# Zoetrope.net
KiCad netlist of a schematic drawn in EAGLE
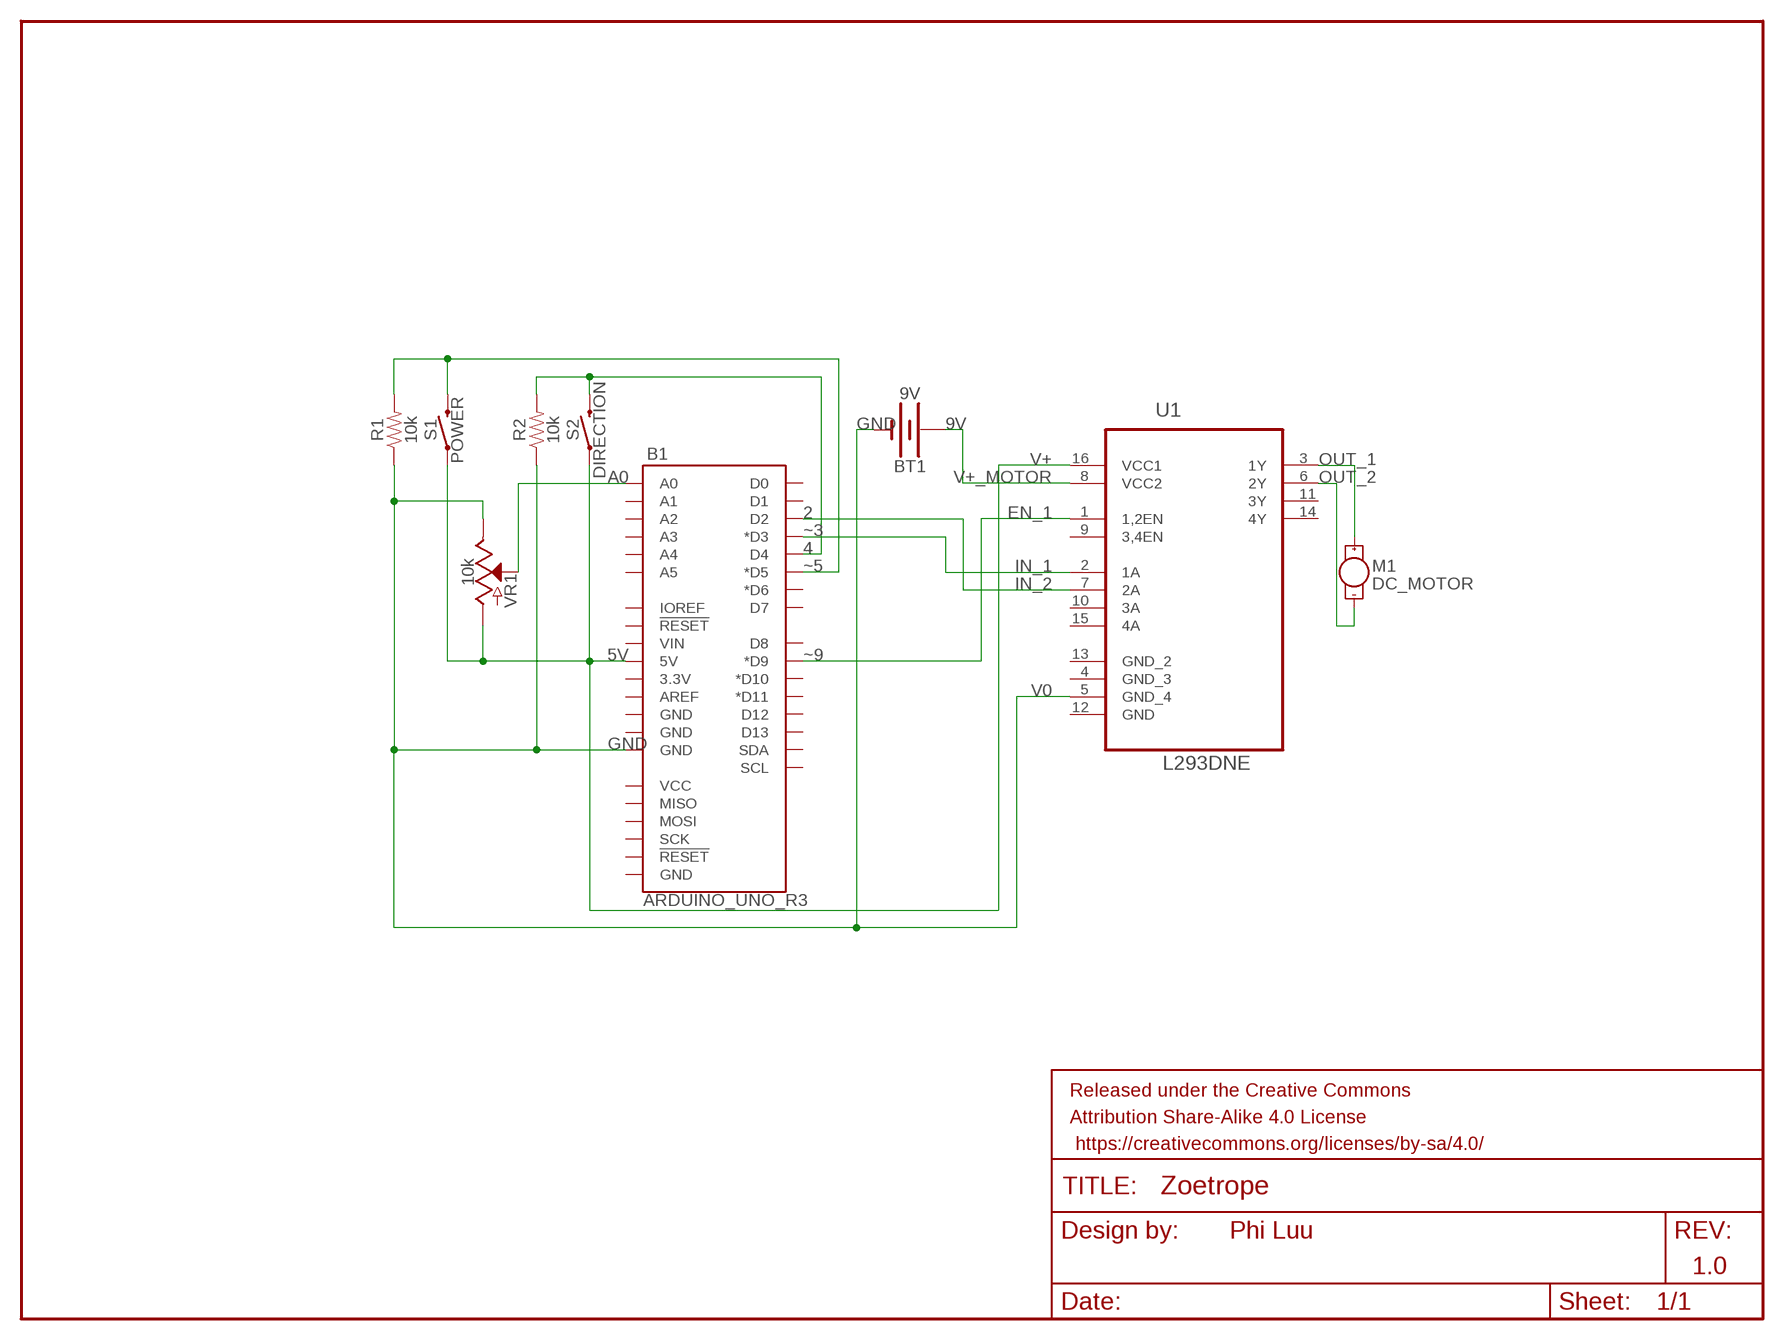
[diagram p0: schematic, sheet 1]

(export (version "E")
  (design (tool "Eeschema 10.0.6"))
  (components
    (comp (ref "B1")
      (value "ARDUINO_UNO_R3")
      (footprint "eagle-import:ARDUINO_R3")
      (libsource (lib "eagle-import") (part "ARDUINO_UNO_R3"))
    )
    (comp (ref "BT1")
      (value "9V")
      (footprint "eagle-import:BATTCON_9V")
      (libsource (lib "eagle-import") (part "BATTERY-9V"))
    )
    (comp (ref "FRAME1")
      (value "FRAME-LETTER")
      (footprint "eagle-import:CREATIVE_COMMONS")
      (libsource (lib "eagle-import") (part "FRAME-LETTER"))
    )
    (comp (ref "M1")
      (value "DC_MOTOR")
      (footprint "eagle-import:VIBE-MOTOR-10MM")
      (libsource (lib "eagle-import") (part "MOTOR10MM"))
    )
    (comp (ref "R1")
      (value "10k")
      (footprint "eagle-import:AXIAL-0.3")
      (libsource (lib "eagle-import") (part "10KOHM-HORIZ-1/4W-5%"))
    )
    (comp (ref "R2")
      (value "10k")
      (footprint "eagle-import:AXIAL-0.3")
      (libsource (lib "eagle-import") (part "10KOHM-HORIZ-1/4W-5%"))
    )
    (comp (ref "S1")
      (value "POWER")
      (footprint "eagle-import:TACTILE_SWITCH_PTH_6.0MM")
      (libsource (lib "eagle-import") (part "MOMENTARY-SWITCH-SPST-PTH-6.0MM"))
    )
    (comp (ref "S2")
      (value "DIRECTION")
      (footprint "eagle-import:TACTILE_SWITCH_PTH_6.0MM")
      (libsource (lib "eagle-import") (part "MOMENTARY-SWITCH-SPST-PTH-6.0MM"))
    )
    (comp (ref "U1")
      (value "L293DNE")
      (footprint "eagle-import:DIP254P762X508-16")
      (libsource (lib "eagle-import") (part "L293DNE"))
    )
    (comp (ref "VR1")
      (value "10k")
      (footprint "eagle-import:POT-PTH-ALPS")
      (libsource (lib "eagle-import") (part "POTENTIOMETER-PTH-9MM-1/20W-20%"))
    )
  )
  (nets
    (net (code "1") (name "/2") (class "Default")
      (node (ref "B1") (pin "D2") (pinfunction "D2_D2") (pintype "bidirectional"))
      (node (ref "U1") (pin "7") (pinfunction "2A_7") (pintype "input"))
    )
    (net (code "2") (name "/4") (class "Default")
      (node (ref "B1") (pin "D4") (pinfunction "D4_D4") (pintype "bidirectional"))
      (node (ref "R2") (pin "P$2") (pinfunction "2_P$2") (pintype "passive"))
      (node (ref "S2") (pin "3") (pinfunction "2_3") (pintype "passive"))
    )
    (net (code "3") (name "/5V") (class "Default")
      (node (ref "B1") (pin "5V") (pinfunction "5V_5V") (pintype "bidirectional"))
      (node (ref "S1") (pin "1") (pinfunction "1_1") (pintype "passive"))
      (node (ref "S2") (pin "1") (pinfunction "1_1") (pintype "passive"))
      (node (ref "U1") (pin "16") (pinfunction "VCC1_16") (pintype "power_in"))
      (node (ref "VR1") (pin "P$3") (pinfunction "A_P$3") (pintype "passive"))
    )
    (net (code "4") (name "/9V") (class "Default")
      (node (ref "BT1") (pin "+") (pinfunction "+_+") (pintype "power_in"))
      (node (ref "U1") (pin "8") (pinfunction "VCC2_8") (pintype "power_in"))
    )
    (net (code "5") (name "/A0") (class "Default")
      (node (ref "B1") (pin "A0") (pinfunction "A0_A0") (pintype "bidirectional"))
      (node (ref "VR1") (pin "P$2") (pinfunction "S_P$2") (pintype "passive"))
    )
    (net (code "6") (name "/GND") (class "Default")
      (node (ref "B1") (pin "GND@2") (pinfunction "GND_GND@2") (pintype "bidirectional"))
      (node (ref "BT1") (pin "-") (pinfunction "-_-") (pintype "power_in"))
      (node (ref "R1") (pin "P$1") (pinfunction "1_P$1") (pintype "passive"))
      (node (ref "R2") (pin "P$1") (pinfunction "1_P$1") (pintype "passive"))
      (node (ref "U1") (pin "5") (pinfunction "GND_4_5") (pintype "passive"))
      (node (ref "VR1") (pin "P$1") (pinfunction "E_P$1") (pintype "passive"))
    )
    (net (code "7") (name "/OUT_1") (class "Default")
      (node (ref "M1") (pin "+") (pinfunction "+_+") (pintype "bidirectional"))
      (node (ref "U1") (pin "3") (pinfunction "1Y_3") (pintype "output"))
    )
    (net (code "8") (name "/OUT_2") (class "Default")
      (node (ref "M1") (pin "-") (pinfunction "-_-") (pintype "bidirectional"))
      (node (ref "U1") (pin "6") (pinfunction "2Y_6") (pintype "output"))
    )
    (net (code "9") (name "/~{3}") (class "Default")
      (node (ref "B1") (pin "D3") (pinfunction "*D3_D3") (pintype "bidirectional"))
      (node (ref "U1") (pin "2") (pinfunction "1A_2") (pintype "input"))
    )
    (net (code "10") (name "/~{5}") (class "Default")
      (node (ref "B1") (pin "D5") (pinfunction "*D5_D5") (pintype "bidirectional"))
      (node (ref "R1") (pin "P$2") (pinfunction "2_P$2") (pintype "passive"))
      (node (ref "S1") (pin "3") (pinfunction "2_3") (pintype "passive"))
    )
    (net (code "11") (name "/~{9}") (class "Default")
      (node (ref "B1") (pin "D9") (pinfunction "*D9_D9") (pintype "bidirectional"))
      (node (ref "U1") (pin "1") (pinfunction "1,2EN_1") (pintype "input"))
    )
    (net (code "12") (name "unconnected-(B1-*D6-PadD6)") (class "Default")
      (node (ref "B1") (pin "D6") (pinfunction "*D6_D6") (pintype "bidirectional"))
    )
    (net (code "13") (name "unconnected-(B1-*D10-PadD10)") (class "Default")
      (node (ref "B1") (pin "D10") (pinfunction "*D10_D10") (pintype "bidirectional"))
    )
    (net (code "14") (name "unconnected-(B1-*D11-PadD11)") (class "Default")
      (node (ref "B1") (pin "D11") (pinfunction "*D11_D11") (pintype "bidirectional"))
    )
    (net (code "15") (name "unconnected-(B1-GND-PadGND@1)") (class "Default")
      (node (ref "B1") (pin "GND@1") (pinfunction "GND_GND@1") (pintype "bidirectional"))
    )
    (net (code "16") (name "unconnected-(B1-GND-PadGND@3)") (class "Default")
      (node (ref "B1") (pin "GND@3") (pinfunction "GND_GND@3") (pintype "bidirectional"))
    )
    (net (code "17") (name "unconnected-(B1-GND-PadGND@4)") (class "Default")
      (node (ref "B1") (pin "GND@4") (pinfunction "GND_GND@4") (pintype "bidirectional"))
    )
    (net (code "18") (name "unconnected-(B1-Pad3.3V)") (class "Default")
      (node (ref "B1") (pin "3.3V") (pinfunction "3.3V_3.3V") (pintype "bidirectional"))
    )
    (net (code "19") (name "unconnected-(B1-PadA1)") (class "Default")
      (node (ref "B1") (pin "A1") (pinfunction "A1_A1") (pintype "bidirectional"))
    )
    (net (code "20") (name "unconnected-(B1-PadA2)") (class "Default")
      (node (ref "B1") (pin "A2") (pinfunction "A2_A2") (pintype "bidirectional"))
    )
    (net (code "21") (name "unconnected-(B1-PadA3)") (class "Default")
      (node (ref "B1") (pin "A3") (pinfunction "A3_A3") (pintype "bidirectional"))
    )
    (net (code "22") (name "unconnected-(B1-PadA4)") (class "Default")
      (node (ref "B1") (pin "A4") (pinfunction "A4_A4") (pintype "bidirectional"))
    )
    (net (code "23") (name "unconnected-(B1-PadA5)") (class "Default")
      (node (ref "B1") (pin "A5") (pinfunction "A5_A5") (pintype "bidirectional"))
    )
    (net (code "24") (name "unconnected-(B1-PadAREF)") (class "Default")
      (node (ref "B1") (pin "AREF") (pinfunction "AREF_AREF") (pintype "bidirectional"))
    )
    (net (code "25") (name "unconnected-(B1-PadD0)") (class "Default")
      (node (ref "B1") (pin "D0") (pinfunction "D0_D0") (pintype "bidirectional"))
    )
    (net (code "26") (name "unconnected-(B1-PadD1)") (class "Default")
      (node (ref "B1") (pin "D1") (pinfunction "D1_D1") (pintype "bidirectional"))
    )
    (net (code "27") (name "unconnected-(B1-PadD7)") (class "Default")
      (node (ref "B1") (pin "D7") (pinfunction "D7_D7") (pintype "bidirectional"))
    )
    (net (code "28") (name "unconnected-(B1-PadD8)") (class "Default")
      (node (ref "B1") (pin "D8") (pinfunction "D8_D8") (pintype "bidirectional"))
    )
    (net (code "29") (name "unconnected-(B1-PadD12)") (class "Default")
      (node (ref "B1") (pin "D12") (pinfunction "D12_D12") (pintype "bidirectional"))
    )
    (net (code "30") (name "unconnected-(B1-PadD13)") (class "Default")
      (node (ref "B1") (pin "D13") (pinfunction "D13_D13") (pintype "bidirectional"))
    )
    (net (code "31") (name "unconnected-(B1-PadIOREF)") (class "Default")
      (node (ref "B1") (pin "IOREF") (pinfunction "IOREF_IOREF") (pintype "bidirectional"))
    )
    (net (code "32") (name "unconnected-(B1-PadMISO)") (class "Default")
      (node (ref "B1") (pin "MISO") (pinfunction "MISO_MISO") (pintype "bidirectional"))
    )
    (net (code "33") (name "unconnected-(B1-PadMOSI)") (class "Default")
      (node (ref "B1") (pin "MOSI") (pinfunction "MOSI_MOSI") (pintype "bidirectional"))
    )
    (net (code "34") (name "unconnected-(B1-PadSCK)") (class "Default")
      (node (ref "B1") (pin "SCK") (pinfunction "SCK_SCK") (pintype "bidirectional"))
    )
    (net (code "35") (name "unconnected-(B1-PadSCL)") (class "Default")
      (node (ref "B1") (pin "SCL") (pinfunction "SCL_SCL") (pintype "bidirectional"))
    )
    (net (code "36") (name "unconnected-(B1-PadSDA)") (class "Default")
      (node (ref "B1") (pin "SDA") (pinfunction "SDA_SDA") (pintype "bidirectional"))
    )
    (net (code "37") (name "unconnected-(B1-PadVCC)") (class "Default")
      (node (ref "B1") (pin "VCC") (pinfunction "VCC_VCC") (pintype "bidirectional"))
    )
    (net (code "38") (name "unconnected-(B1-PadVIN)") (class "Default")
      (node (ref "B1") (pin "VIN") (pinfunction "VIN_VIN") (pintype "bidirectional"))
    )
    (net (code "39") (name "unconnected-(B1-~{RESET}-PadRESET@1)") (class "Default")
      (node (ref "B1") (pin "RESET@1") (pinfunction "~{RESET}_RESET@1") (pintype "bidirectional"))
    )
    (net (code "40") (name "unconnected-(B1-~{RESET}-PadRESET@2)") (class "Default")
      (node (ref "B1") (pin "RESET@2") (pinfunction "~{RESET}_RESET@2") (pintype "bidirectional"))
    )
    (net (code "41") (name "unconnected-(U1-3,4EN-Pad9)") (class "Default")
      (node (ref "U1") (pin "9") (pinfunction "3,4EN_9") (pintype "input"))
    )
    (net (code "42") (name "unconnected-(U1-3A-Pad10)") (class "Default")
      (node (ref "U1") (pin "10") (pinfunction "3A_10") (pintype "input"))
    )
    (net (code "43") (name "unconnected-(U1-3Y-Pad11)") (class "Default")
      (node (ref "U1") (pin "11") (pinfunction "3Y_11") (pintype "output"))
    )
    (net (code "44") (name "unconnected-(U1-4A-Pad15)") (class "Default")
      (node (ref "U1") (pin "15") (pinfunction "4A_15") (pintype "input"))
    )
    (net (code "45") (name "unconnected-(U1-4Y-Pad14)") (class "Default")
      (node (ref "U1") (pin "14") (pinfunction "4Y_14") (pintype "output"))
    )
    (net (code "46") (name "unconnected-(U1-GND-Pad12)") (class "Default")
      (node (ref "U1") (pin "12") (pinfunction "GND_12") (pintype "passive"))
    )
    (net (code "47") (name "unconnected-(U1-GND_2-Pad13)") (class "Default")
      (node (ref "U1") (pin "13") (pinfunction "GND_2_13") (pintype "passive"))
    )
    (net (code "48") (name "unconnected-(U1-GND_3-Pad4)") (class "Default")
      (node (ref "U1") (pin "4") (pinfunction "GND_3_4") (pintype "passive"))
    )
  )
)
